# 1_ESP32.net
KiCad netlist of a schematic drawn in Altium Designer
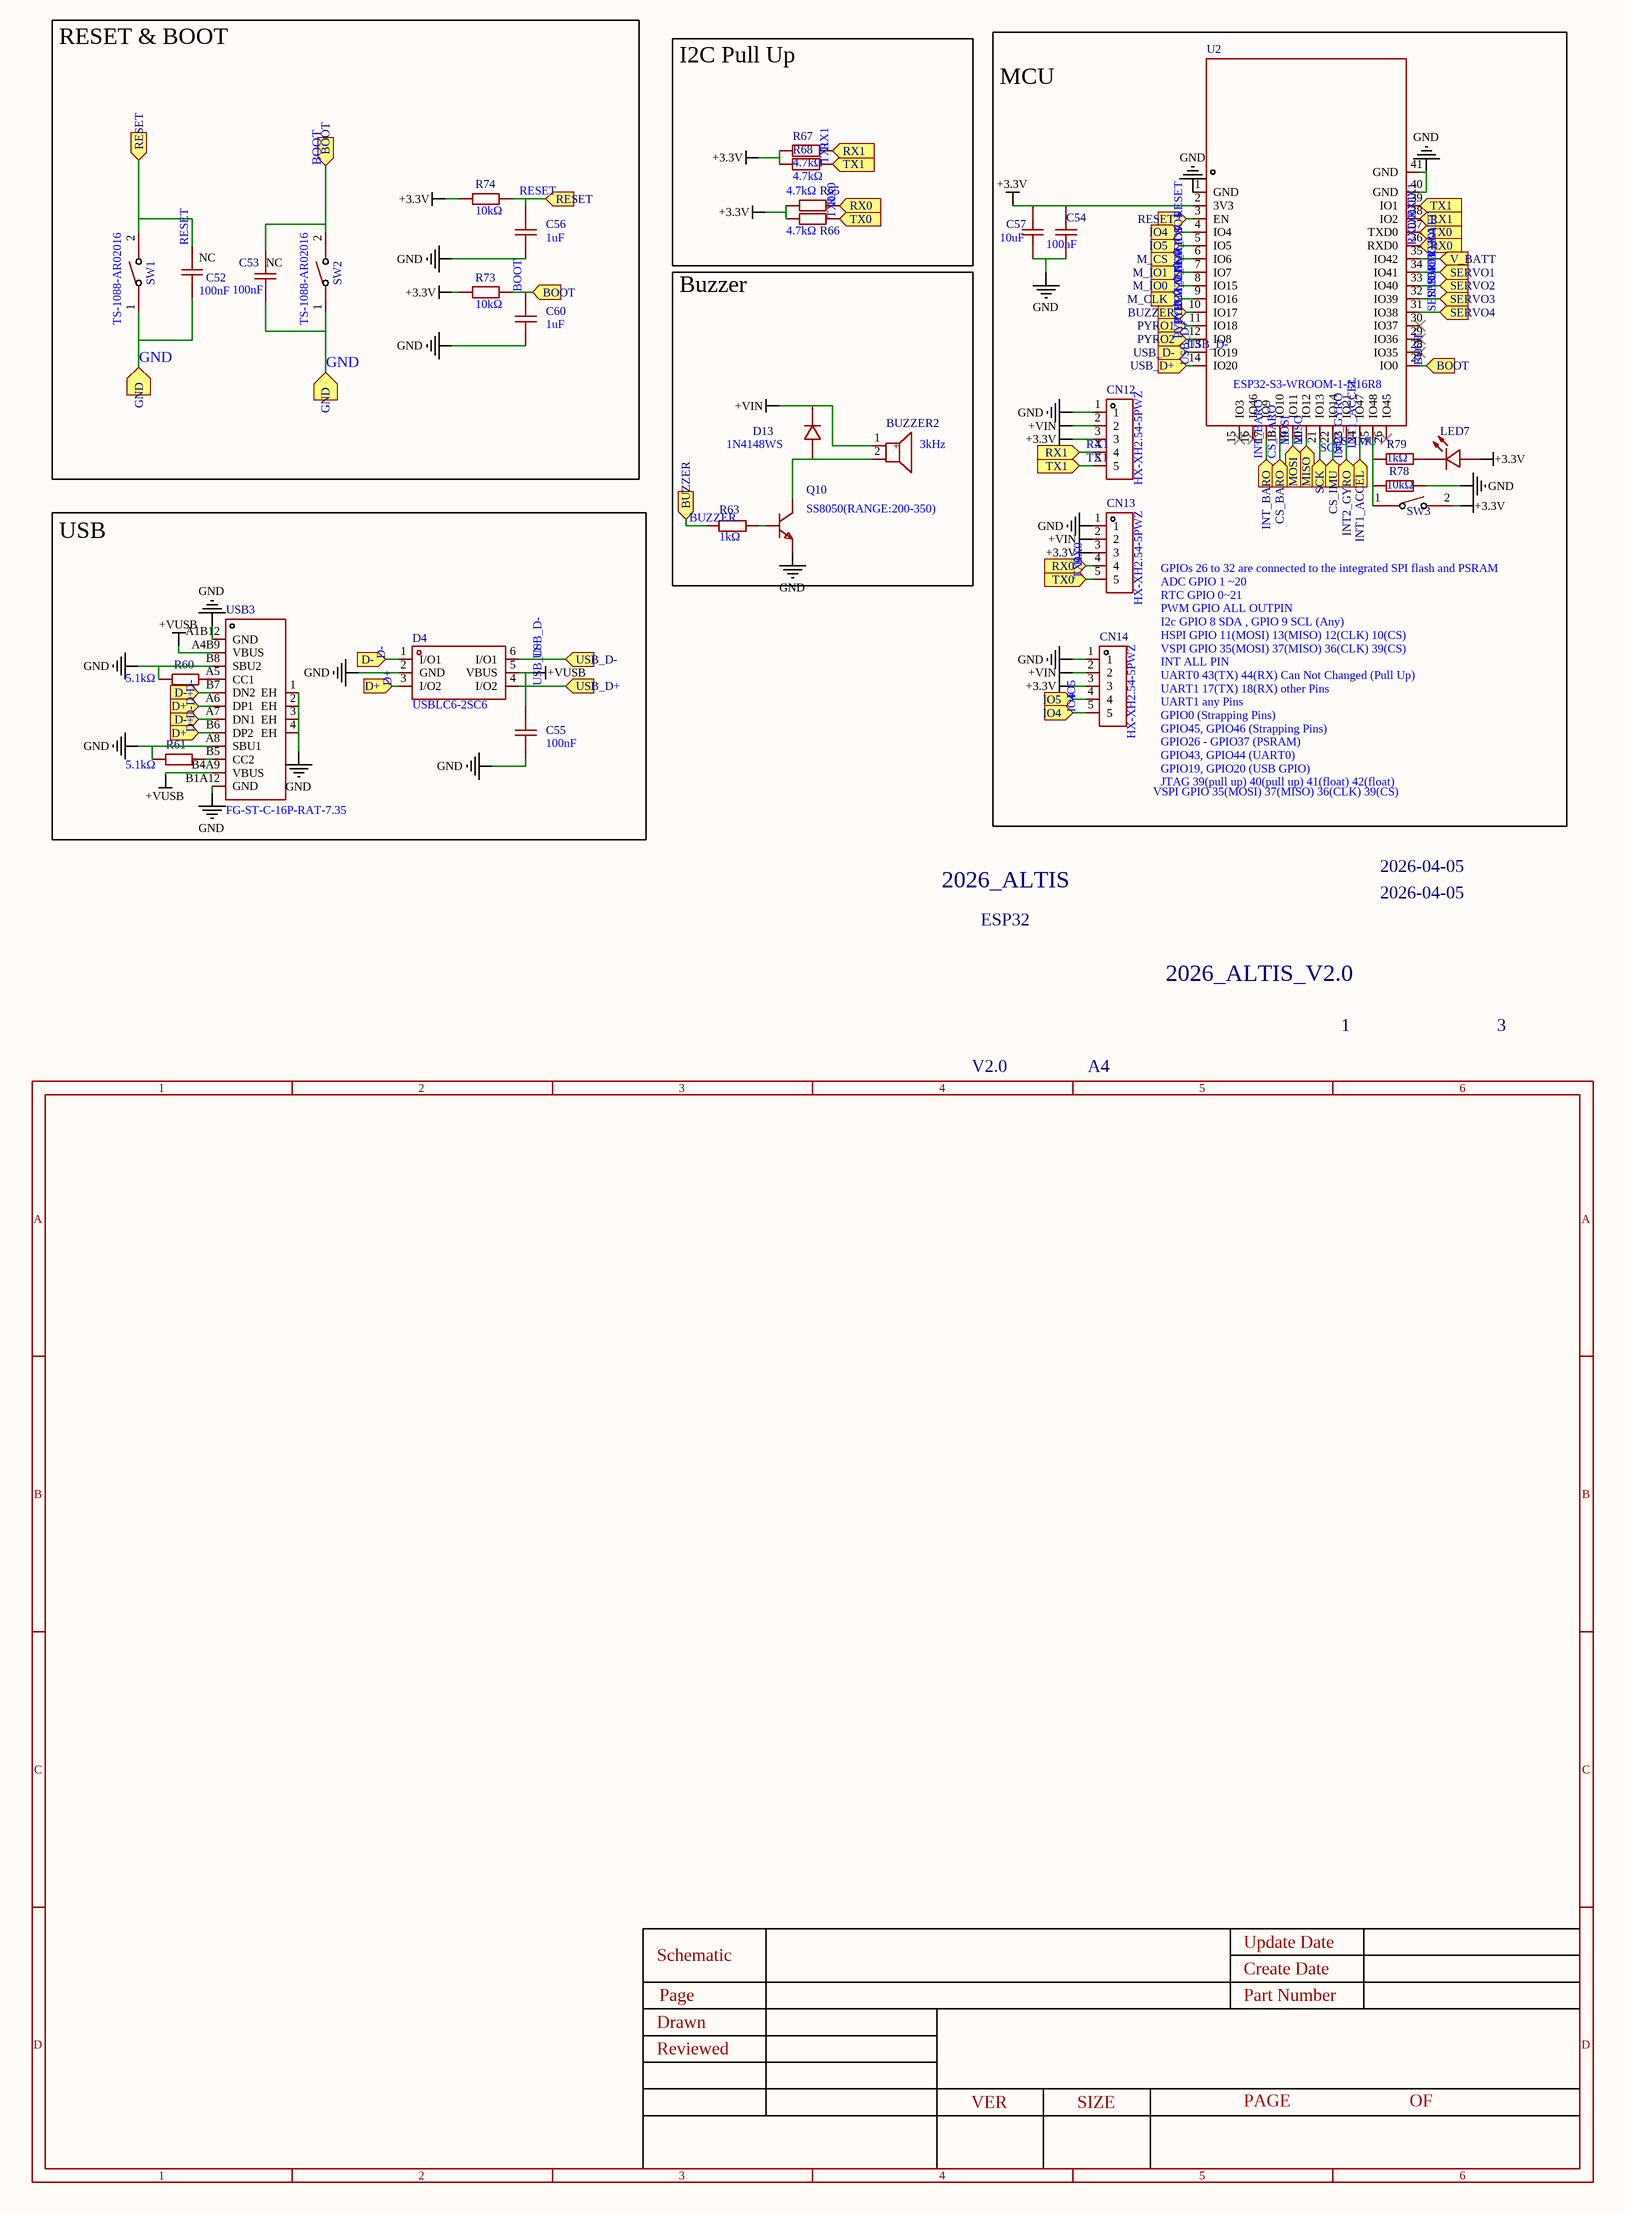
[diagram p0: 1_ESP32.schdoc]

(export (version "E")
  (design (tool "Eeschema 10.0.6"))
  (components
    (comp (ref "BUZZER2")
      (value "3kHz")
      (footprint "BUZ-TH_BD9.6-P5.00-D0.7-FD")
      (fields (field (name "MANUFACTURER") "华能") (field (name "MANUFACTURER PART") "HNB09A05"))
      (libsource (lib "altium-import") (part "root_0_HNB09A05_"))
    )
    (comp (ref "C52")
      (value "100nF")
      (footprint "C0603")
      (fields
        (field (name "MANUFACTURER") "YAGEO(国巨)")
        (field (name "MANUFACTURER PART") "CC0603KRX7R9BB104")
        (field (name "TOLERANCE") "±10%")
      )
      (libsource (lib "altium-import") (part "root_1_CC0603KRX7R9BB104_"))
    )
    (comp (ref "C53")
      (value "100nF")
      (footprint "C0603")
      (fields
        (field (name "MANUFACTURER") "YAGEO(国巨)")
        (field (name "MANUFACTURER PART") "CC0603KRX7R9BB104")
        (field (name "TOLERANCE") "±10%")
      )
      (libsource (lib "altium-import") (part "root_1_CC0603KRX7R9BB104_"))
    )
    (comp (ref "C54")
      (value "100nF")
      (footprint "C0603")
      (fields
        (field (name "MANUFACTURER") "YAGEO(国巨)")
        (field (name "MANUFACTURER PART") "CC0603KRX7R9BB104")
        (field (name "TOLERANCE") "±10%")
      )
      (libsource (lib "altium-import") (part "root_1_CC0603KRX7R9BB104_"))
    )
    (comp (ref "C55")
      (value "100nF")
      (footprint "C0603")
      (fields
        (field (name "MANUFACTURER") "YAGEO(国巨)")
        (field (name "MANUFACTURER PART") "CC0603KRX7R9BB104")
        (field (name "TOLERANCE") "±10%")
      )
      (libsource (lib "altium-import") (part "root_1_CC0603KRX7R9BB104_"))
    )
    (comp (ref "C56")
      (value "1uF")
      (footprint "C0603")
      (fields
        (field (name "MANUFACTURER") "SAMSUNG(三星)")
        (field (name "MANUFACTURER PART") "CL10A105KB8NNNC")
        (field (name "TOLERANCE") "±10%")
      )
      (libsource (lib "altium-import") (part "root_1_CL10A105KB8NNNC_"))
    )
    (comp (ref "C57")
      (value "10uF")
      (footprint "C0603")
      (fields
        (field (name "MANUFACTURER") "SAMSUNG(三星)")
        (field (name "MANUFACTURER PART") "CL10A106KP8NNNC")
        (field (name "TOLERANCE") "±10%")
      )
      (libsource (lib "altium-import") (part "root_1_CL10A106KP8NNNC_"))
    )
    (comp (ref "C60")
      (value "1uF")
      (footprint "C0603")
      (fields
        (field (name "MANUFACTURER") "SAMSUNG(三星)")
        (field (name "MANUFACTURER PART") "CL10A105KB8NNNC")
        (field (name "TOLERANCE") "±10%")
      )
      (libsource (lib "altium-import") (part "root_1_CL10A105KB8NNNC_"))
    )
    (comp (ref "CN12")
      (value "HX-XH2.54-5PWZ")
      (footprint "CONN-TH_HX-XH2.54-5PWZ")
      (fields (field (name "MANUFACTURER") "hanxia(韩下)"))
      (libsource (lib "altium-import") (part "root_0_HX-XH2.54-5PWZ_"))
    )
    (comp (ref "CN13")
      (value "HX-XH2.54-5PWZ")
      (footprint "CONN-TH_HX-XH2.54-5PWZ")
      (fields (field (name "MANUFACTURER") "hanxia(韩下)"))
      (libsource (lib "altium-import") (part "root_0_HX-XH2.54-5PWZ_"))
    )
    (comp (ref "CN14")
      (value "HX-XH2.54-5PWZ")
      (footprint "CONN-TH_HX-XH2.54-5PWZ")
      (fields (field (name "MANUFACTURER") "hanxia(韩下)"))
      (libsource (lib "altium-import") (part "root_0_HX-XH2.54-5PWZ_"))
    )
    (comp (ref "D4")
      (value "USBLC6-2SC6")
      (footprint "SOT-23-6_L2.9-W1.6-P0.95-LS2.8-BL")
      (fields (field (name "MANUFACTURER") "UMW(友台半导体)"))
      (libsource (lib "altium-import") (part "root_0_USBLC6-2SC6_C2687116_"))
    )
    (comp (ref "D13")
      (value "1N4148WS")
      (footprint "SOD-323_L1.8-W1.3-LS2.5-RD")
      (fields (field (name "MANUFACTURER") "CJ(江苏长电/长晶)"))
      (libsource (lib "altium-import") (part "root_3_1N4148WS_C2128_"))
    )
    (comp (ref "LED7")
      (value "KT-0603R")
      (footprint "LED0603-RD")
      (fields (field (name "MANUFACTURER") "KENTO"))
      (libsource (lib "altium-import") (part "root_0_KT-0603R_"))
    )
    (comp (ref "Q10")
      (value "SS8050(RANGE:200-350)")
      (footprint "SOT-23-3_L2.9-W1.3-P1.90-LS2.4-BR")
      (fields (field (name "MANUFACTURER") "CJ(江苏长电/长晶)"))
      (libsource (lib "altium-import") (part "root_0_SS8050(RANGE{colon}200-350)_C2150_"))
    )
    (comp (ref "R60")
      (value "5.1kΩ")
      (footprint "R0603")
      (fields
        (field (name "MANUFACTURER") "UNI-ROYAL(厚声)")
        (field (name "MANUFACTURER PART") "0603WAF5101T5E")
        (field (name "TOLERANCE") "±1%")
      )
      (libsource (lib "altium-import") (part "root_2_0603WAF5101T5E_"))
    )
    (comp (ref "R61")
      (value "5.1kΩ")
      (footprint "R0603")
      (fields
        (field (name "MANUFACTURER") "UNI-ROYAL(厚声)")
        (field (name "MANUFACTURER PART") "0603WAF5101T5E")
        (field (name "TOLERANCE") "±1%")
      )
      (libsource (lib "altium-import") (part "root_2_0603WAF5101T5E_"))
    )
    (comp (ref "R63")
      (value "1kΩ")
      (footprint "R0603")
      (fields
        (field (name "MANUFACTURER") "UNI-ROYAL(厚声)")
        (field (name "MANUFACTURER PART") "0603WAF1001T5E")
        (field (name "TOLERANCE") "±1%")
      )
      (libsource (lib "altium-import") (part "root_0_0603WAF1001T5E_"))
    )
    (comp (ref "R65")
      (value "4.7kΩ")
      (footprint "R0603")
      (fields
        (field (name "MANUFACTURER") "UNI-ROYAL(厚声)")
        (field (name "MANUFACTURER PART") "0603WAF4701T5E")
        (field (name "TOLERANCE") "±1%")
      )
      (libsource (lib "altium-import") (part "root_2_0603WAF4701T5E_"))
    )
    (comp (ref "R66")
      (value "4.7kΩ")
      (footprint "R0603")
      (fields
        (field (name "MANUFACTURER") "UNI-ROYAL(厚声)")
        (field (name "MANUFACTURER PART") "0603WAF4701T5E")
        (field (name "TOLERANCE") "±1%")
      )
      (libsource (lib "altium-import") (part "root_2_0603WAF4701T5E_"))
    )
    (comp (ref "R67")
      (value "4.7kΩ")
      (footprint "R0603")
      (fields
        (field (name "MANUFACTURER") "UNI-ROYAL(厚声)")
        (field (name "MANUFACTURER PART") "0603WAF4701T5E")
        (field (name "TOLERANCE") "±1%")
      )
      (libsource (lib "altium-import") (part "root_2_0603WAF4701T5E_"))
    )
    (comp (ref "R68")
      (value "4.7kΩ")
      (footprint "R0603")
      (fields
        (field (name "MANUFACTURER") "UNI-ROYAL(厚声)")
        (field (name "MANUFACTURER PART") "0603WAF4701T5E")
        (field (name "TOLERANCE") "±1%")
      )
      (libsource (lib "altium-import") (part "root_2_0603WAF4701T5E_"))
    )
    (comp (ref "R73")
      (value "10kΩ")
      (footprint "R0603")
      (fields
        (field (name "MANUFACTURER") "UNI-ROYAL(厚声)")
        (field (name "MANUFACTURER PART") "0603WAF1002T5E")
        (field (name "TOLERANCE") "±1%")
      )
      (libsource (lib "altium-import") (part "root_2_0603WAF1002T5E_"))
    )
    (comp (ref "R74")
      (value "10kΩ")
      (footprint "R0603")
      (fields
        (field (name "MANUFACTURER") "UNI-ROYAL(厚声)")
        (field (name "MANUFACTURER PART") "0603WAF1002T5E")
        (field (name "TOLERANCE") "±1%")
      )
      (libsource (lib "altium-import") (part "root_2_0603WAF1002T5E_"))
    )
    (comp (ref "R78")
      (value "10kΩ")
      (footprint "R0603")
      (fields
        (field (name "MANUFACTURER") "UNI-ROYAL(厚声)")
        (field (name "MANUFACTURER PART") "0603WAF1002T5E")
        (field (name "TOLERANCE") "±1%")
      )
      (libsource (lib "altium-import") (part "root_2_0603WAF1002T5E_"))
    )
    (comp (ref "R79")
      (value "1kΩ")
      (footprint "R0603")
      (fields
        (field (name "MANUFACTURER") "UNI-ROYAL(厚声)")
        (field (name "MANUFACTURER PART") "0603WAF1001T5E")
        (field (name "TOLERANCE") "±1%")
      )
      (libsource (lib "altium-import") (part "root_2_0603WAF1001T5E_"))
    )
    (comp (ref "SW1")
      (value "TS-1088-AR02016")
      (footprint "SW-SMD_L3.9-W3.0-P4.45")
      (fields (field (name "MANUFACTURER") "XUNPU(讯普)"))
      (libsource (lib "altium-import") (part "root_1_TS-1088-AR02016_"))
    )
    (comp (ref "SW2")
      (value "TS-1088-AR02016")
      (footprint "SW-SMD_L3.9-W3.0-P4.45")
      (fields (field (name "MANUFACTURER") "XUNPU(讯普)"))
      (libsource (lib "altium-import") (part "root_1_TS-1088-AR02016_"))
    )
    (comp (ref "SW3")
      (value "TS-1088-AR02016")
      (footprint "SW-SMD_L3.9-W3.0-P4.45")
      (fields (field (name "MANUFACTURER") "XUNPU(讯普)"))
      (libsource (lib "altium-import") (part "root_0_TS-1088-AR02016_"))
    )
    (comp (ref "U2")
      (value "ESP32-S3-WROOM-1-N16R8")
      (footprint "WIRELM-SMD_ESP32-S3-WROOM-1")
      (fields (field (name "MANUFACTURER") "ESPRESSIF(乐鑫)"))
      (libsource (lib "altium-import") (part "root_0_ESP32-S3-WROOM-1-N16R8_"))
    )
    (comp (ref "USB3")
      (value "FG-ST-C-16P-RAT-7.35")
      (footprint "USB-C-SMD_FG-ST-C-16P-RAT-7.35")
      (fields (field (name "MANUFACTURER") "FG(富港)"))
      (libsource (lib "altium-import") (part "root_0_FG-ST-C-16P-RAT-7.35_"))
    )
  )
  (nets
    (net (code "1") (name "+3.3V") (class "Default")
      (node (ref "C54") (pin "2") (pinfunction "2_2") (pintype "passive"))
      (node (ref "C57") (pin "2") (pinfunction "2_2") (pintype "passive"))
      (node (ref "CN12") (pin "3") (pinfunction "3_3") (pintype "passive"))
      (node (ref "CN13") (pin "3") (pinfunction "3_3") (pintype "passive"))
      (node (ref "CN14") (pin "3") (pinfunction "3_3") (pintype "passive"))
      (node (ref "LED7") (pin "2") (pinfunction "A_2") (pintype "passive"))
      (node (ref "R65") (pin "2") (pinfunction "2_2") (pintype "passive"))
      (node (ref "R66") (pin "2") (pinfunction "2_2") (pintype "passive"))
      (node (ref "R67") (pin "2") (pinfunction "2_2") (pintype "passive"))
      (node (ref "R68") (pin "2") (pinfunction "2_2") (pintype "passive"))
      (node (ref "R73") (pin "2") (pinfunction "2_2") (pintype "passive"))
      (node (ref "R74") (pin "2") (pinfunction "2_2") (pintype "passive"))
      (node (ref "SW3") (pin "2") (pinfunction "2_2") (pintype "passive"))
      (node (ref "U2") (pin "2") (pinfunction "3V3_2") (pintype "passive"))
    )
    (net (code "2") (name "+VIN") (class "Default")
      (node (ref "BUZZER2") (pin "1") (pinfunction "+_1") (pintype "passive"))
      (node (ref "CN12") (pin "2") (pinfunction "2_2") (pintype "passive"))
      (node (ref "CN13") (pin "2") (pinfunction "2_2") (pintype "passive"))
      (node (ref "CN14") (pin "2") (pinfunction "2_2") (pintype "passive"))
      (node (ref "D13") (pin "1") (pinfunction "K_1") (pintype "passive"))
    )
    (net (code "3") (name "+VUSB") (class "Default")
      (node (ref "C55") (pin "2") (pinfunction "2_2") (pintype "passive"))
      (node (ref "D4") (pin "5") (pinfunction "VBUS_5") (pintype "passive"))
      (node (ref "USB3") (pin "A4B9") (pinfunction "VBUS_A4B9") (pintype "passive"))
      (node (ref "USB3") (pin "B4A9") (pinfunction "VBUS_B4A9") (pintype "passive"))
    )
    (net (code "4") (name "/BOOT") (class "Default")
      (node (ref "C53") (pin "2") (pinfunction "2_2") (pintype "passive"))
      (node (ref "C60") (pin "2") (pinfunction "2_2") (pintype "passive"))
      (node (ref "R73") (pin "1") (pinfunction "1_1") (pintype "passive"))
      (node (ref "SW2") (pin "2") (pinfunction "2_2") (pintype "passive"))
      (node (ref "U2") (pin "27") (pinfunction "IO0_27") (pintype "passive"))
    )
    (net (code "5") (name "/BUZZER") (class "Default")
      (node (ref "R63") (pin "1") (pinfunction "1_1") (pintype "passive"))
      (node (ref "U2") (pin "10") (pinfunction "IO17_10") (pintype "passive"))
    )
    (net (code "6") (name "/CS_BARO") (class "Default")
      (node (ref "U2") (pin "18") (pinfunction "IO10_18") (pintype "passive"))
    )
    (net (code "7") (name "/CS_IMU") (class "Default")
      (node (ref "U2") (pin "22") (pinfunction "IO14_22") (pintype "passive"))
    )
    (net (code "8") (name "/D+") (class "Default")
      (node (ref "D4") (pin "3") (pinfunction "I/O2_3") (pintype "passive"))
      (node (ref "USB3") (pin "A6") (pinfunction "DP1_A6") (pintype "passive"))
      (node (ref "USB3") (pin "B6") (pinfunction "DP2_B6") (pintype "passive"))
    )
    (net (code "9") (name "/D-") (class "Default")
      (node (ref "D4") (pin "1") (pinfunction "I/O1_1") (pintype "passive"))
      (node (ref "USB3") (pin "A7") (pinfunction "DN1_A7") (pintype "passive"))
      (node (ref "USB3") (pin "B7") (pinfunction "DN2_B7") (pintype "passive"))
    )
    (net (code "10") (name "/INT1_ACCEL") (class "Default")
      (node (ref "U2") (pin "24") (pinfunction "IO47_24") (pintype "passive"))
    )
    (net (code "11") (name "/INT2_GYRO") (class "Default")
      (node (ref "U2") (pin "23") (pinfunction "IO21_23") (pintype "passive"))
    )
    (net (code "12") (name "/INT_BARO") (class "Default")
      (node (ref "U2") (pin "17") (pinfunction "IO9_17") (pintype "passive"))
    )
    (net (code "13") (name "/IO4") (class "Default")
      (node (ref "CN14") (pin "5") (pinfunction "5_5") (pintype "passive"))
      (node (ref "U2") (pin "4") (pinfunction "IO4_4") (pintype "passive"))
    )
    (net (code "14") (name "/IO5") (class "Default")
      (node (ref "CN14") (pin "4") (pinfunction "4_4") (pintype "passive"))
      (node (ref "U2") (pin "5") (pinfunction "IO5_5") (pintype "passive"))
    )
    (net (code "15") (name "/MISO") (class "Default")
      (node (ref "U2") (pin "20") (pinfunction "IO12_20") (pintype "passive"))
    )
    (net (code "16") (name "/MOSI") (class "Default")
      (node (ref "U2") (pin "19") (pinfunction "IO11_19") (pintype "passive"))
    )
    (net (code "17") (name "/M_CLK") (class "Default")
      (node (ref "U2") (pin "9") (pinfunction "IO16_9") (pintype "passive"))
    )
    (net (code "18") (name "/M_CS") (class "Default")
      (node (ref "U2") (pin "6") (pinfunction "IO6_6") (pintype "passive"))
    )
    (net (code "19") (name "/M_IO0") (class "Default")
      (node (ref "U2") (pin "8") (pinfunction "IO15_8") (pintype "passive"))
    )
    (net (code "20") (name "/M_IO1") (class "Default")
      (node (ref "U2") (pin "7") (pinfunction "IO7_7") (pintype "passive"))
    )
    (net (code "21") (name "/PYRO1") (class "Default")
      (node (ref "U2") (pin "11") (pinfunction "IO18_11") (pintype "passive"))
    )
    (net (code "22") (name "/PYRO2") (class "Default")
      (node (ref "U2") (pin "12") (pinfunction "IO8_12") (pintype "passive"))
    )
    (net (code "23") (name "/RESET") (class "Default")
      (node (ref "C52") (pin "2") (pinfunction "2_2") (pintype "passive"))
      (node (ref "C56") (pin "2") (pinfunction "2_2") (pintype "passive"))
      (node (ref "R74") (pin "1") (pinfunction "1_1") (pintype "passive"))
      (node (ref "SW1") (pin "2") (pinfunction "2_2") (pintype "passive"))
      (node (ref "U2") (pin "3") (pinfunction "EN_3") (pintype "passive"))
    )
    (net (code "24") (name "/RX0") (class "Default")
      (node (ref "CN13") (pin "4") (pinfunction "4_4") (pintype "passive"))
      (node (ref "R65") (pin "1") (pinfunction "1_1") (pintype "passive"))
      (node (ref "U2") (pin "36") (pinfunction "RXD0_36") (pintype "passive"))
    )
    (net (code "25") (name "/RX1") (class "Default")
      (node (ref "CN12") (pin "4") (pinfunction "4_4") (pintype "passive"))
      (node (ref "R67") (pin "1") (pinfunction "1_1") (pintype "passive"))
      (node (ref "U2") (pin "38") (pinfunction "IO2_38") (pintype "passive"))
    )
    (net (code "26") (name "/SCK") (class "Default")
      (node (ref "U2") (pin "21") (pinfunction "IO13_21") (pintype "passive"))
    )
    (net (code "27") (name "/SERVO1") (class "Default")
      (node (ref "U2") (pin "34") (pinfunction "IO41_34") (pintype "passive"))
    )
    (net (code "28") (name "/SERVO2") (class "Default")
      (node (ref "U2") (pin "33") (pinfunction "IO40_33") (pintype "passive"))
    )
    (net (code "29") (name "/SERVO3") (class "Default")
      (node (ref "U2") (pin "32") (pinfunction "IO39_32") (pintype "passive"))
    )
    (net (code "30") (name "/SERVO4") (class "Default")
      (node (ref "U2") (pin "31") (pinfunction "IO38_31") (pintype "passive"))
    )
    (net (code "31") (name "/TX0") (class "Default")
      (node (ref "CN13") (pin "5") (pinfunction "5_5") (pintype "passive"))
      (node (ref "R66") (pin "1") (pinfunction "1_1") (pintype "passive"))
      (node (ref "U2") (pin "37") (pinfunction "TXD0_37") (pintype "passive"))
    )
    (net (code "32") (name "/TX1") (class "Default")
      (node (ref "CN12") (pin "5") (pinfunction "5_5") (pintype "passive"))
      (node (ref "R68") (pin "1") (pinfunction "1_1") (pintype "passive"))
      (node (ref "U2") (pin "39") (pinfunction "IO1_39") (pintype "passive"))
    )
    (net (code "33") (name "/USB_D+") (class "Default")
      (node (ref "D4") (pin "4") (pinfunction "I/O2_4") (pintype "passive"))
      (node (ref "U2") (pin "14") (pinfunction "IO20_14") (pintype "passive"))
    )
    (net (code "34") (name "/USB_D-") (class "Default")
      (node (ref "D4") (pin "6") (pinfunction "I/O1_6") (pintype "passive"))
      (node (ref "U2") (pin "13") (pinfunction "IO19_13") (pintype "passive"))
    )
    (net (code "35") (name "/V_BATT") (class "Default")
      (node (ref "U2") (pin "35") (pinfunction "IO42_35") (pintype "passive"))
    )
    (net (code "36") (name "GND") (class "Default")
      (node (ref "C52") (pin "1") (pinfunction "1_1") (pintype "passive"))
      (node (ref "C53") (pin "1") (pinfunction "1_1") (pintype "passive"))
      (node (ref "C54") (pin "1") (pinfunction "1_1") (pintype "passive"))
      (node (ref "C55") (pin "1") (pinfunction "1_1") (pintype "passive"))
      (node (ref "C56") (pin "1") (pinfunction "1_1") (pintype "passive"))
      (node (ref "C57") (pin "1") (pinfunction "1_1") (pintype "passive"))
      (node (ref "C60") (pin "1") (pinfunction "1_1") (pintype "passive"))
      (node (ref "CN12") (pin "1") (pinfunction "1_1") (pintype "passive"))
      (node (ref "CN13") (pin "1") (pinfunction "1_1") (pintype "passive"))
      (node (ref "CN14") (pin "1") (pinfunction "1_1") (pintype "passive"))
      (node (ref "D4") (pin "2") (pinfunction "GND_2") (pintype "passive"))
      (node (ref "Q10") (pin "2") (pinfunction "E_2") (pintype "passive"))
      (node (ref "R60") (pin "2") (pinfunction "2_2") (pintype "passive"))
      (node (ref "R61") (pin "2") (pinfunction "2_2") (pintype "passive"))
      (node (ref "R78") (pin "1") (pinfunction "1_1") (pintype "passive"))
      (node (ref "SW1") (pin "1") (pinfunction "1_1") (pintype "passive"))
      (node (ref "SW2") (pin "1") (pinfunction "1_1") (pintype "passive"))
      (node (ref "U2") (pin "1") (pinfunction "GND_1") (pintype "passive"))
      (node (ref "U2") (pin "40") (pinfunction "GND_40") (pintype "passive"))
      (node (ref "U2") (pin "41") (pinfunction "GND_41") (pintype "passive"))
      (node (ref "USB3") (pin "1") (pinfunction "EH_1") (pintype "passive"))
      (node (ref "USB3") (pin "2") (pinfunction "EH_2") (pintype "passive"))
      (node (ref "USB3") (pin "3") (pinfunction "EH_3") (pintype "passive"))
      (node (ref "USB3") (pin "4") (pinfunction "EH_4") (pintype "passive"))
      (node (ref "USB3") (pin "A1B12") (pinfunction "GND_A1B12") (pintype "passive"))
      (node (ref "USB3") (pin "A8") (pinfunction "SBU1_A8") (pintype "passive"))
      (node (ref "USB3") (pin "B1A12") (pinfunction "GND_B1A12") (pintype "passive"))
      (node (ref "USB3") (pin "B8") (pinfunction "SBU2_B8") (pintype "passive"))
    )
    (net (code "37") (name "Net-(D13-A)") (class "Default")
      (node (ref "BUZZER2") (pin "2") (pinfunction "2_2") (pintype "passive"))
      (node (ref "D13") (pin "2") (pinfunction "A_2") (pintype "passive"))
      (node (ref "Q10") (pin "3") (pinfunction "C_3") (pintype "passive"))
    )
    (net (code "38") (name "Net-(LED7-K)") (class "Default")
      (node (ref "LED7") (pin "1") (pinfunction "K_1") (pintype "passive"))
      (node (ref "R79") (pin "1") (pinfunction "1_1") (pintype "passive"))
    )
    (net (code "39") (name "Net-(Q10-B)") (class "Default")
      (node (ref "Q10") (pin "1") (pinfunction "B_1") (pintype "passive"))
      (node (ref "R63") (pin "2") (pinfunction "2_2") (pintype "passive"))
    )
    (net (code "40") (name "Net-(U2-IO48)") (class "Default")
      (node (ref "R78") (pin "2") (pinfunction "2_2") (pintype "passive"))
      (node (ref "R79") (pin "2") (pinfunction "2_2") (pintype "passive"))
      (node (ref "SW3") (pin "1") (pinfunction "1_1") (pintype "passive"))
      (node (ref "U2") (pin "25") (pinfunction "IO48_25") (pintype "passive"))
    )
    (net (code "41") (name "Net-(USB3-CC1)") (class "Default")
      (node (ref "R60") (pin "1") (pinfunction "1_1") (pintype "passive"))
      (node (ref "USB3") (pin "A5") (pinfunction "CC1_A5") (pintype "passive"))
    )
    (net (code "42") (name "Net-(USB3-CC2)") (class "Default")
      (node (ref "R61") (pin "1") (pinfunction "1_1") (pintype "passive"))
      (node (ref "USB3") (pin "B5") (pinfunction "CC2_B5") (pintype "passive"))
    )
    (net (code "43") (name "unconnected-(U2-IO3-Pad15)") (class "Default")
      (node (ref "U2") (pin "15") (pinfunction "IO3_15") (pintype "passive+no_connect"))
    )
    (net (code "44") (name "unconnected-(U2-IO35-Pad28)") (class "Default")
      (node (ref "U2") (pin "28") (pinfunction "IO35_28") (pintype "passive+no_connect"))
    )
    (net (code "45") (name "unconnected-(U2-IO36-Pad29)") (class "Default")
      (node (ref "U2") (pin "29") (pinfunction "IO36_29") (pintype "passive+no_connect"))
    )
    (net (code "46") (name "unconnected-(U2-IO37-Pad30)") (class "Default")
      (node (ref "U2") (pin "30") (pinfunction "IO37_30") (pintype "passive+no_connect"))
    )
    (net (code "47") (name "unconnected-(U2-IO45-Pad26)") (class "Default")
      (node (ref "U2") (pin "26") (pinfunction "IO45_26") (pintype "passive+no_connect"))
    )
    (net (code "48") (name "unconnected-(U2-IO46-Pad16)") (class "Default")
      (node (ref "U2") (pin "16") (pinfunction "IO46_16") (pintype "passive+no_connect"))
    )
  )
)
